# Sheet1.net
KiCad netlist of a schematic drawn in Altium Designer
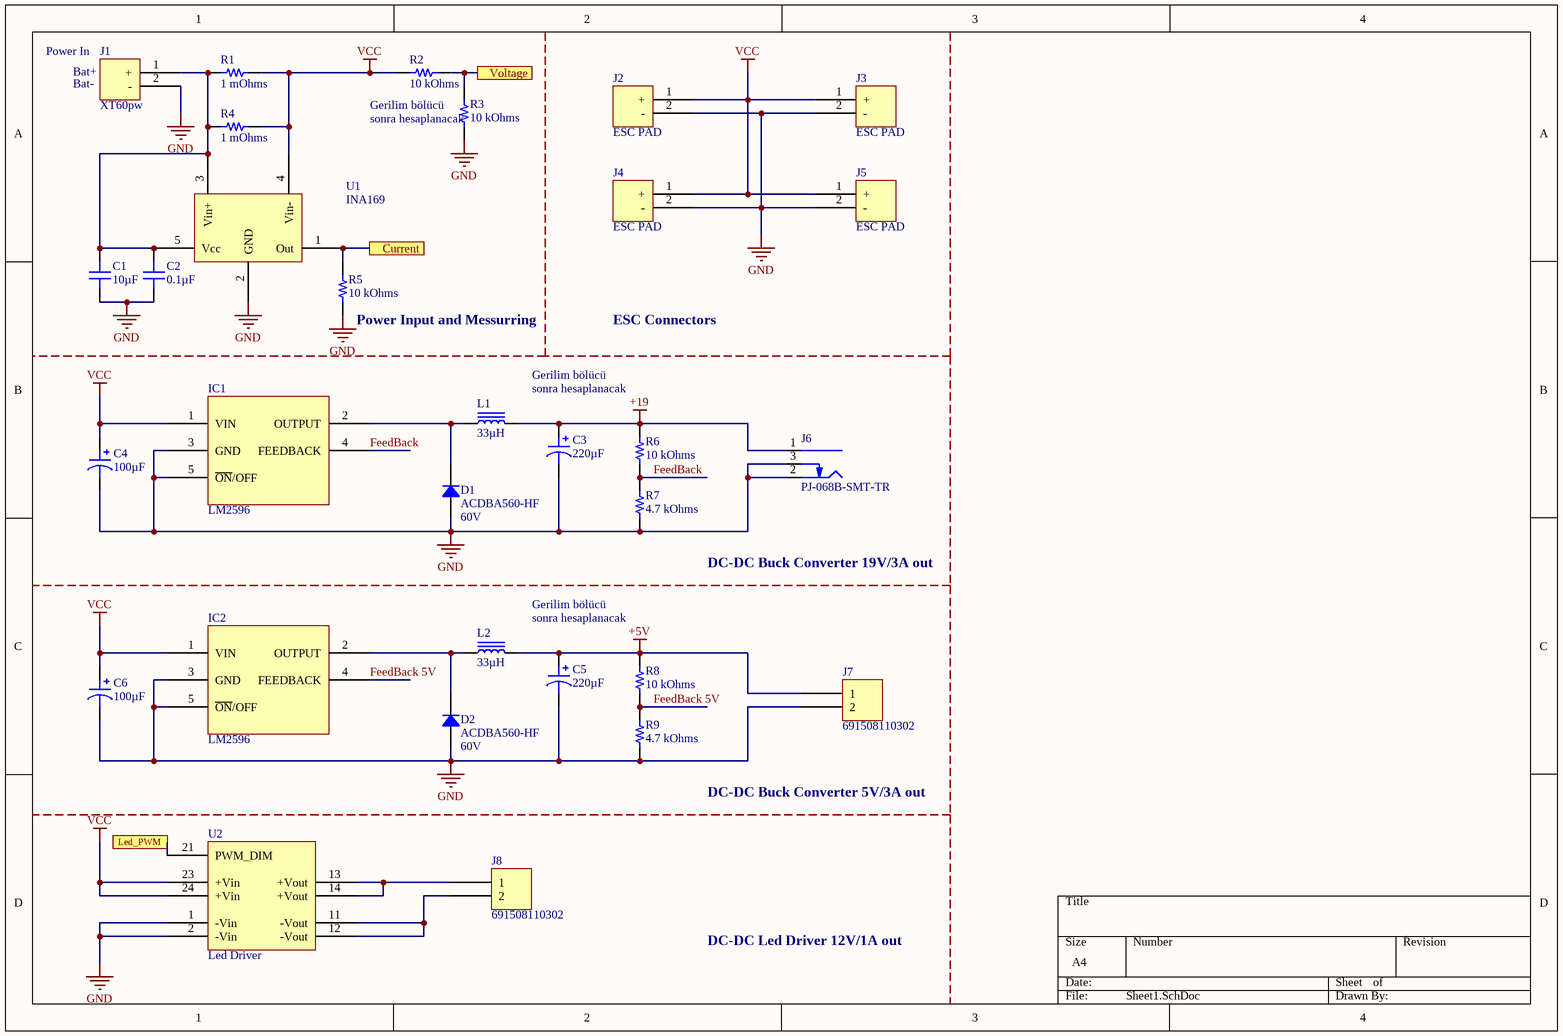
[diagram p0: Sheet1.SchDoc]

(export (version "E")
  (design (tool "Eeschema 10.0.6"))
  (components
    (comp (ref "C1")
      (value "10µF")
      (footprint "CAP 0603_1608")
      (description "CAP CER 10UF 35V X5R 0603")
      (fields
        (field (name "PART NUMBER") "GRM188R6YA106MA73D")
        (field (name "MANUFACTURER") "Murata Electronics")
      )
      (libsource (lib "Celestial Altium Library - altium_library") (part "Capacitor"))
    )
    (comp (ref "C2")
      (value "0.1µF")
      (footprint "CAP 0603_1608")
      (description "CAP CER 0.1UF 35V X5R 0603")
      (fields (field (name "PART NUMBER") "GMK107BJ104KAHT") (field (name "MANUFACTURER") "Taiyo Yuden"))
      (libsource (lib "Celestial Altium Library - altium_library") (part "Capacitor"))
    )
    (comp (ref "C3")
      (value "220µF")
      (footprint "CAP ALSMD 8.3MM H10.5MM")
      (description "CAP ALUM 220UF 20% 35V SMD")
      (fields
        (field (name "PART NUMBER") "EEE-FK1V221GP")
        (field (name "MANUFACTURER") "Panasonic Electronic Components")
      )
      (libsource (lib "Celestial Altium Library - altium_library") (part "Polarised Capacitor"))
    )
    (comp (ref "C4")
      (value "100µF")
      (footprint "CAP ALSMD 8.3MM H10.5MM")
      (description "CAP ALUM 100UF 20% 35V SMD")
      (fields (field (name "PART NUMBER") "UCD1V101MNL1GS") (field (name "MANUFACTURER") "Nichicon"))
      (libsource (lib "Celestial Altium Library - altium_library") (part "Polarised Capacitor"))
    )
    (comp (ref "C5")
      (value "220µF")
      (footprint "CAP ALSMD 8.3MM H10.5MM")
      (description "CAP ALUM 220UF 20% 35V SMD")
      (fields
        (field (name "PART NUMBER") "EEE-FK1V221GP")
        (field (name "MANUFACTURER") "Panasonic Electronic Components")
      )
      (libsource (lib "Celestial Altium Library - altium_library") (part "Polarised Capacitor"))
    )
    (comp (ref "C6")
      (value "100µF")
      (footprint "CAP ALSMD 8.3MM H10.5MM")
      (description "CAP ALUM 100UF 20% 35V SMD")
      (fields (field (name "PART NUMBER") "UCD1V101MNL1GS") (field (name "MANUFACTURER") "Nichicon"))
      (libsource (lib "Celestial Altium Library - altium_library") (part "Polarised Capacitor"))
    )
    (comp (ref "D1")
      (value "ACDBA560-HF")
      (footprint "DO214AC SMA")
      (description "DIODE SCHOTTKY 60V 5A DO214AC")
      (fields
        (field (name "MANUFACTURER") "Comchip Technology")
        (field (name "VOLTAGE - DC REVERSE (VR) (MAX)") "60V")
      )
      (libsource (lib "Celestial Altium Library - altium_library") (part "Diode"))
    )
    (comp (ref "D2")
      (value "ACDBA560-HF")
      (footprint "DO214AC SMA")
      (description "DIODE SCHOTTKY 60V 5A DO214AC")
      (fields
        (field (name "MANUFACTURER") "Comchip Technology")
        (field (name "VOLTAGE - DC REVERSE (VR) (MAX)") "60V")
      )
      (libsource (lib "Celestial Altium Library - altium_library") (part "Diode"))
    )
    (comp (ref "IC1") (value "LM2596") (footprint "D2PAK") (libsource (lib "Schlib1") (part "LM2596")))
    (comp (ref "IC2") (value "LM2596") (footprint "D2PAK") (libsource (lib "Schlib1") (part "LM2596")))
    (comp (ref "J1")
      (value "XT60pw")
      (footprint "XT60_90degree")
      (description "xt60 90 degree Connector")
      (libsource (lib "Schlib1") (part "XT60PW-M"))
    )
    (comp (ref "J2")
      (value "ESC PAD")
      (footprint "ESC Connector")
      (libsource (lib "") (part "ESC Connector_1"))
    )
    (comp (ref "J3")
      (value "ESC PAD")
      (footprint "ESC Connector")
      (libsource (lib "Schlib1") (part "ESC Connector"))
    )
    (comp (ref "J4")
      (value "ESC PAD")
      (footprint "ESC Connector")
      (libsource (lib "") (part "ESC Connector_1"))
    )
    (comp (ref "J5")
      (value "ESC PAD")
      (footprint "ESC Connector")
      (libsource (lib "Schlib1") (part "ESC Connector"))
    )
    (comp (ref "J6")
      (value "PJ-068B-SMT-TR")
      (footprint "CUI PJ-068B-SMT")
      (description "CONN PWR JACK 2.5X5.5MM SOLDER")
      (fields (field (name "MANUFACTURER") "CUI Devices"))
      (libsource (lib "Celestial Altium Library - altium_library") (part "Barrel Connector"))
    )
    (comp (ref "J7")
      (value "691508110302")
      (footprint "WURTH 691508110302")
      (description "TERM BLOCK 2POS 3.5MM SMD")
      (fields (field (name "MANUFACTURER") "Würth Elektronik") (field (name "VOLTAGE") "300V"))
      (libsource (lib "Celestial Altium Library - altium_library") (part "2 Pin"))
    )
    (comp (ref "J8")
      (value "691508110302")
      (footprint "WURTH 691508110302")
      (description "TERM BLOCK 2POS 3.5MM SMD")
      (fields (field (name "MANUFACTURER") "Würth Elektronik") (field (name "VOLTAGE") "300V"))
      (libsource (lib "Celestial Altium Library - altium_library") (part "2 Pin"))
    )
    (comp (ref "L1")
      (value "33µH")
      (footprint "BOURNS SRR1280")
      (description "FIXED IND 33UH 3.5A 57 MOHM SMD")
      (fields (field (name "PART NUMBER") "SRR1280-330M") (field (name "MANUFACTURER") "Bourns Inc."))
      (libsource (lib "Celestial Altium Library - altium_library") (part "Inductor"))
    )
    (comp (ref "L2")
      (value "33µH")
      (footprint "BOURNS SRR1280")
      (description "FIXED IND 33UH 3.5A 57 MOHM SMD")
      (fields (field (name "PART NUMBER") "SRR1280-330M") (field (name "MANUFACTURER") "Bourns Inc."))
      (libsource (lib "Celestial Altium Library - altium_library") (part "Inductor"))
    )
    (comp (ref "R1")
      (value "1 mOhms")
      (footprint "VISHAY WSHP2818")
      (description "RES 0.001 OHM 1% 10W 2818")
      (fields (field (name "PART NUMBER") "WSHP28181L000FEA") (field (name "MANUFACTURER") "Vishay Dale"))
      (libsource (lib "Celestial Altium Library - altium_library") (part "Resistor"))
    )
    (comp (ref "R2")
      (value "10 kOhms")
      (footprint "RES 0603_1608")
      (description "RES 10K OHM 0.1% 1/16W 0603")
      (fields
        (field (name "PART NUMBER") "RNCS0603BKE10K0")
        (field (name "MANUFACTURER") "Stackpole Electronics Inc")
      )
      (libsource (lib "Celestial Altium Library - altium_library") (part "Resistor"))
    )
    (comp (ref "R3")
      (value "10 kOhms")
      (footprint "RES 0603_1608")
      (description "RES 10K OHM 0.1% 1/16W 0603")
      (fields
        (field (name "PART NUMBER") "RNCS0603BKE10K0")
        (field (name "MANUFACTURER") "Stackpole Electronics Inc")
      )
      (libsource (lib "Celestial Altium Library - altium_library") (part "Resistor"))
    )
    (comp (ref "R4")
      (value "1 mOhms")
      (footprint "VISHAY WSHP2818")
      (description "RES 0.001 OHM 1% 10W 2818")
      (fields (field (name "PART NUMBER") "WSHP28181L000FEA") (field (name "MANUFACTURER") "Vishay Dale"))
      (libsource (lib "Celestial Altium Library - altium_library") (part "Resistor"))
    )
    (comp (ref "R5")
      (value "10 kOhms")
      (footprint "RES 0603_1608")
      (description "RES 10K OHM 0.1% 1/16W 0603")
      (fields
        (field (name "PART NUMBER") "RNCS0603BKE10K0")
        (field (name "MANUFACTURER") "Stackpole Electronics Inc")
      )
      (libsource (lib "Celestial Altium Library - altium_library") (part "Resistor"))
    )
    (comp (ref "R6")
      (value "10 kOhms")
      (footprint "RES 0805_2012")
      (description "RES 10K OHM 1% 1/4W 0805")
      (fields
        (field (name "PART NUMBER") "RNCP0805FTD10K0")
        (field (name "MANUFACTURER") "Stackpole Electronics Inc")
      )
      (libsource (lib "Celestial Altium Library - altium_library") (part "Resistor"))
    )
    (comp (ref "R7")
      (value "4.7 kOhms")
      (footprint "RES 0805_2012")
      (description "CRGP 0805 4K7 1%")
      (fields
        (field (name "PART NUMBER") "CRGP0805F4K7")
        (field (name "MANUFACTURER") "TE Connectivity Passive Product")
      )
      (libsource (lib "Celestial Altium Library - altium_library") (part "Resistor"))
    )
    (comp (ref "R8")
      (value "10 kOhms")
      (footprint "RES 0805_2012")
      (description "RES 10K OHM 1% 1/4W 0805")
      (fields
        (field (name "PART NUMBER") "RNCP0805FTD10K0")
        (field (name "MANUFACTURER") "Stackpole Electronics Inc")
      )
      (libsource (lib "Celestial Altium Library - altium_library") (part "Resistor"))
    )
    (comp (ref "R9")
      (value "4.7 kOhms")
      (footprint "RES 0805_2012")
      (description "CRGP 0805 4K7 1%")
      (fields
        (field (name "PART NUMBER") "CRGP0805F4K7")
        (field (name "MANUFACTURER") "TE Connectivity Passive Product")
      )
      (libsource (lib "Celestial Altium Library - altium_library") (part "Resistor"))
    )
    (comp (ref "U1")
      (value "INA169")
      (footprint "INA169")
      (description "Current sensing IC")
      (libsource (lib "Schlib1") (part "INA169"))
    )
    (comp (ref "U2")
      (value "Led Driver")
      (footprint "LDD100l")
      (description "LDD 1000L 12V 1A")
      (libsource (lib "Schlib1") (part "LDD1000L"))
    )
  )
  (nets
    (net (code "1") (name "+5V") (class "Default")
      (node (ref "C5") (pin "1") (pinfunction "1_1") (pintype "passive"))
      (node (ref "J7") (pin "1") (pinfunction "1_1") (pintype "passive"))
      (node (ref "L2") (pin "2") (pinfunction "2_2") (pintype "passive"))
      (node (ref "R8") (pin "2") (pinfunction "2_2") (pintype "passive"))
    )
    (net (code "2") (name "+19") (class "Default")
      (node (ref "C3") (pin "1") (pinfunction "1_1") (pintype "passive"))
      (node (ref "J6") (pin "1") (pinfunction "Centre_1") (pintype "passive"))
      (node (ref "L1") (pin "2") (pinfunction "2_2") (pintype "passive"))
      (node (ref "R6") (pin "2") (pinfunction "2_2") (pintype "passive"))
    )
    (net (code "3") (name "/Current") (class "Default")
      (node (ref "R5") (pin "2") (pinfunction "2_2") (pintype "passive"))
      (node (ref "U1") (pin "1") (pinfunction "Out_1") (pintype "passive"))
    )
    (net (code "4") (name "/FeedBack") (class "Default")
      (node (ref "IC1") (pin "4") (pinfunction "FEEDBACK_4") (pintype "passive"))
      (node (ref "R6") (pin "1") (pinfunction "1_1") (pintype "passive"))
      (node (ref "R7") (pin "2") (pinfunction "2_2") (pintype "passive"))
    )
    (net (code "5") (name "/FeedBack 5V") (class "Default")
      (node (ref "IC2") (pin "4") (pinfunction "FEEDBACK_4") (pintype "passive"))
      (node (ref "R8") (pin "1") (pinfunction "1_1") (pintype "passive"))
      (node (ref "R9") (pin "2") (pinfunction "2_2") (pintype "passive"))
    )
    (net (code "6") (name "/Led_PWM") (class "Default")
      (node (ref "U2") (pin "21") (pinfunction "PWM_DIM_21") (pintype "passive"))
    )
    (net (code "7") (name "/Voltage") (class "Default")
      (node (ref "R2") (pin "1") (pinfunction "1_1") (pintype "passive"))
      (node (ref "R3") (pin "2") (pinfunction "2_2") (pintype "passive"))
    )
    (net (code "8") (name "GND") (class "Default")
      (node (ref "C1") (pin "1") (pinfunction "1_1") (pintype "passive"))
      (node (ref "C2") (pin "1") (pinfunction "1_1") (pintype "passive"))
      (node (ref "C3") (pin "2") (pinfunction "2_2") (pintype "passive"))
      (node (ref "C4") (pin "2") (pinfunction "2_2") (pintype "passive"))
      (node (ref "C5") (pin "2") (pinfunction "2_2") (pintype "passive"))
      (node (ref "C6") (pin "2") (pinfunction "2_2") (pintype "passive"))
      (node (ref "D1") (pin "1") (pinfunction "1_1") (pintype "passive"))
      (node (ref "D2") (pin "1") (pinfunction "1_1") (pintype "passive"))
      (node (ref "IC1") (pin "3") (pinfunction "GND_3") (pintype "passive"))
      (node (ref "IC1") (pin "5") (pinfunction "~{ON}/OFF_5") (pintype "passive"))
      (node (ref "IC2") (pin "3") (pinfunction "GND_3") (pintype "passive"))
      (node (ref "IC2") (pin "5") (pinfunction "~{ON}/OFF_5") (pintype "passive"))
      (node (ref "J1") (pin "2") (pinfunction "-_2") (pintype "passive"))
      (node (ref "J2") (pin "2") (pinfunction "-_2") (pintype "passive"))
      (node (ref "J3") (pin "2") (pinfunction "-_2") (pintype "passive"))
      (node (ref "J4") (pin "2") (pinfunction "-_2") (pintype "passive"))
      (node (ref "J5") (pin "2") (pinfunction "-_2") (pintype "passive"))
      (node (ref "J6") (pin "2") (pinfunction "Outer_2") (pintype "passive"))
      (node (ref "J6") (pin "3") (pinfunction "SW_3") (pintype "passive"))
      (node (ref "J7") (pin "2") (pinfunction "2_2") (pintype "passive"))
      (node (ref "R3") (pin "1") (pinfunction "1_1") (pintype "passive"))
      (node (ref "R5") (pin "1") (pinfunction "1_1") (pintype "passive"))
      (node (ref "R7") (pin "1") (pinfunction "1_1") (pintype "passive"))
      (node (ref "R9") (pin "1") (pinfunction "1_1") (pintype "passive"))
      (node (ref "U1") (pin "2") (pinfunction "GND_2") (pintype "passive"))
      (node (ref "U2") (pin "1") (pinfunction "-Vin_1") (pintype "passive"))
      (node (ref "U2") (pin "2") (pinfunction "-Vin_2") (pintype "passive"))
    )
    (net (code "9") (name "Net-(IC1-OUTPUT)") (class "Default")
      (node (ref "D1") (pin "2") (pinfunction "2_2") (pintype "passive"))
      (node (ref "IC1") (pin "2") (pinfunction "OUTPUT_2") (pintype "passive"))
      (node (ref "L1") (pin "1") (pinfunction "1_1") (pintype "passive"))
    )
    (net (code "10") (name "Net-(IC2-OUTPUT)") (class "Default")
      (node (ref "D2") (pin "2") (pinfunction "2_2") (pintype "passive"))
      (node (ref "IC2") (pin "2") (pinfunction "OUTPUT_2") (pintype "passive"))
      (node (ref "L2") (pin "1") (pinfunction "1_1") (pintype "passive"))
    )
    (net (code "11") (name "Net-(J1-+)") (class "Default")
      (node (ref "C1") (pin "2") (pinfunction "2_2") (pintype "passive"))
      (node (ref "C2") (pin "2") (pinfunction "2_2") (pintype "passive"))
      (node (ref "J1") (pin "1") (pinfunction "+_1") (pintype "passive"))
      (node (ref "R1") (pin "1") (pinfunction "1_1") (pintype "passive"))
      (node (ref "R4") (pin "1") (pinfunction "1_1") (pintype "passive"))
      (node (ref "U1") (pin "3") (pinfunction "Vin+_3") (pintype "passive"))
      (node (ref "U1") (pin "5") (pinfunction "Vcc_5") (pintype "passive"))
    )
    (net (code "12") (name "Net-(J8-Pad1)") (class "Default")
      (node (ref "J8") (pin "1") (pinfunction "1_1") (pintype "passive"))
      (node (ref "U2") (pin "13") (pinfunction "+Vout_13") (pintype "passive"))
      (node (ref "U2") (pin "14") (pinfunction "+Vout_14") (pintype "passive"))
    )
    (net (code "13") (name "Net-(J8-Pad2)") (class "Default")
      (node (ref "J8") (pin "2") (pinfunction "2_2") (pintype "passive"))
      (node (ref "U2") (pin "11") (pinfunction "-Vout_11") (pintype "passive"))
      (node (ref "U2") (pin "12") (pinfunction "-Vout_12") (pintype "passive"))
    )
    (net (code "14") (name "VCC") (class "Default")
      (node (ref "C4") (pin "1") (pinfunction "1_1") (pintype "passive"))
      (node (ref "C6") (pin "1") (pinfunction "1_1") (pintype "passive"))
      (node (ref "IC1") (pin "1") (pinfunction "VIN_1") (pintype "passive"))
      (node (ref "IC2") (pin "1") (pinfunction "VIN_1") (pintype "passive"))
      (node (ref "J2") (pin "1") (pinfunction "+_1") (pintype "passive"))
      (node (ref "J3") (pin "1") (pinfunction "+_1") (pintype "passive"))
      (node (ref "J4") (pin "1") (pinfunction "+_1") (pintype "passive"))
      (node (ref "J5") (pin "1") (pinfunction "+_1") (pintype "passive"))
      (node (ref "R1") (pin "2") (pinfunction "2_2") (pintype "passive"))
      (node (ref "R2") (pin "2") (pinfunction "2_2") (pintype "passive"))
      (node (ref "R4") (pin "2") (pinfunction "2_2") (pintype "passive"))
      (node (ref "U1") (pin "4") (pinfunction "Vin-_4") (pintype "passive"))
      (node (ref "U2") (pin "23") (pinfunction "+Vin_23") (pintype "passive"))
      (node (ref "U2") (pin "24") (pinfunction "+Vin_24") (pintype "passive"))
    )
  )
)
